# design.net
KiCad netlist of a schematic drawn in EasyEDA Pro
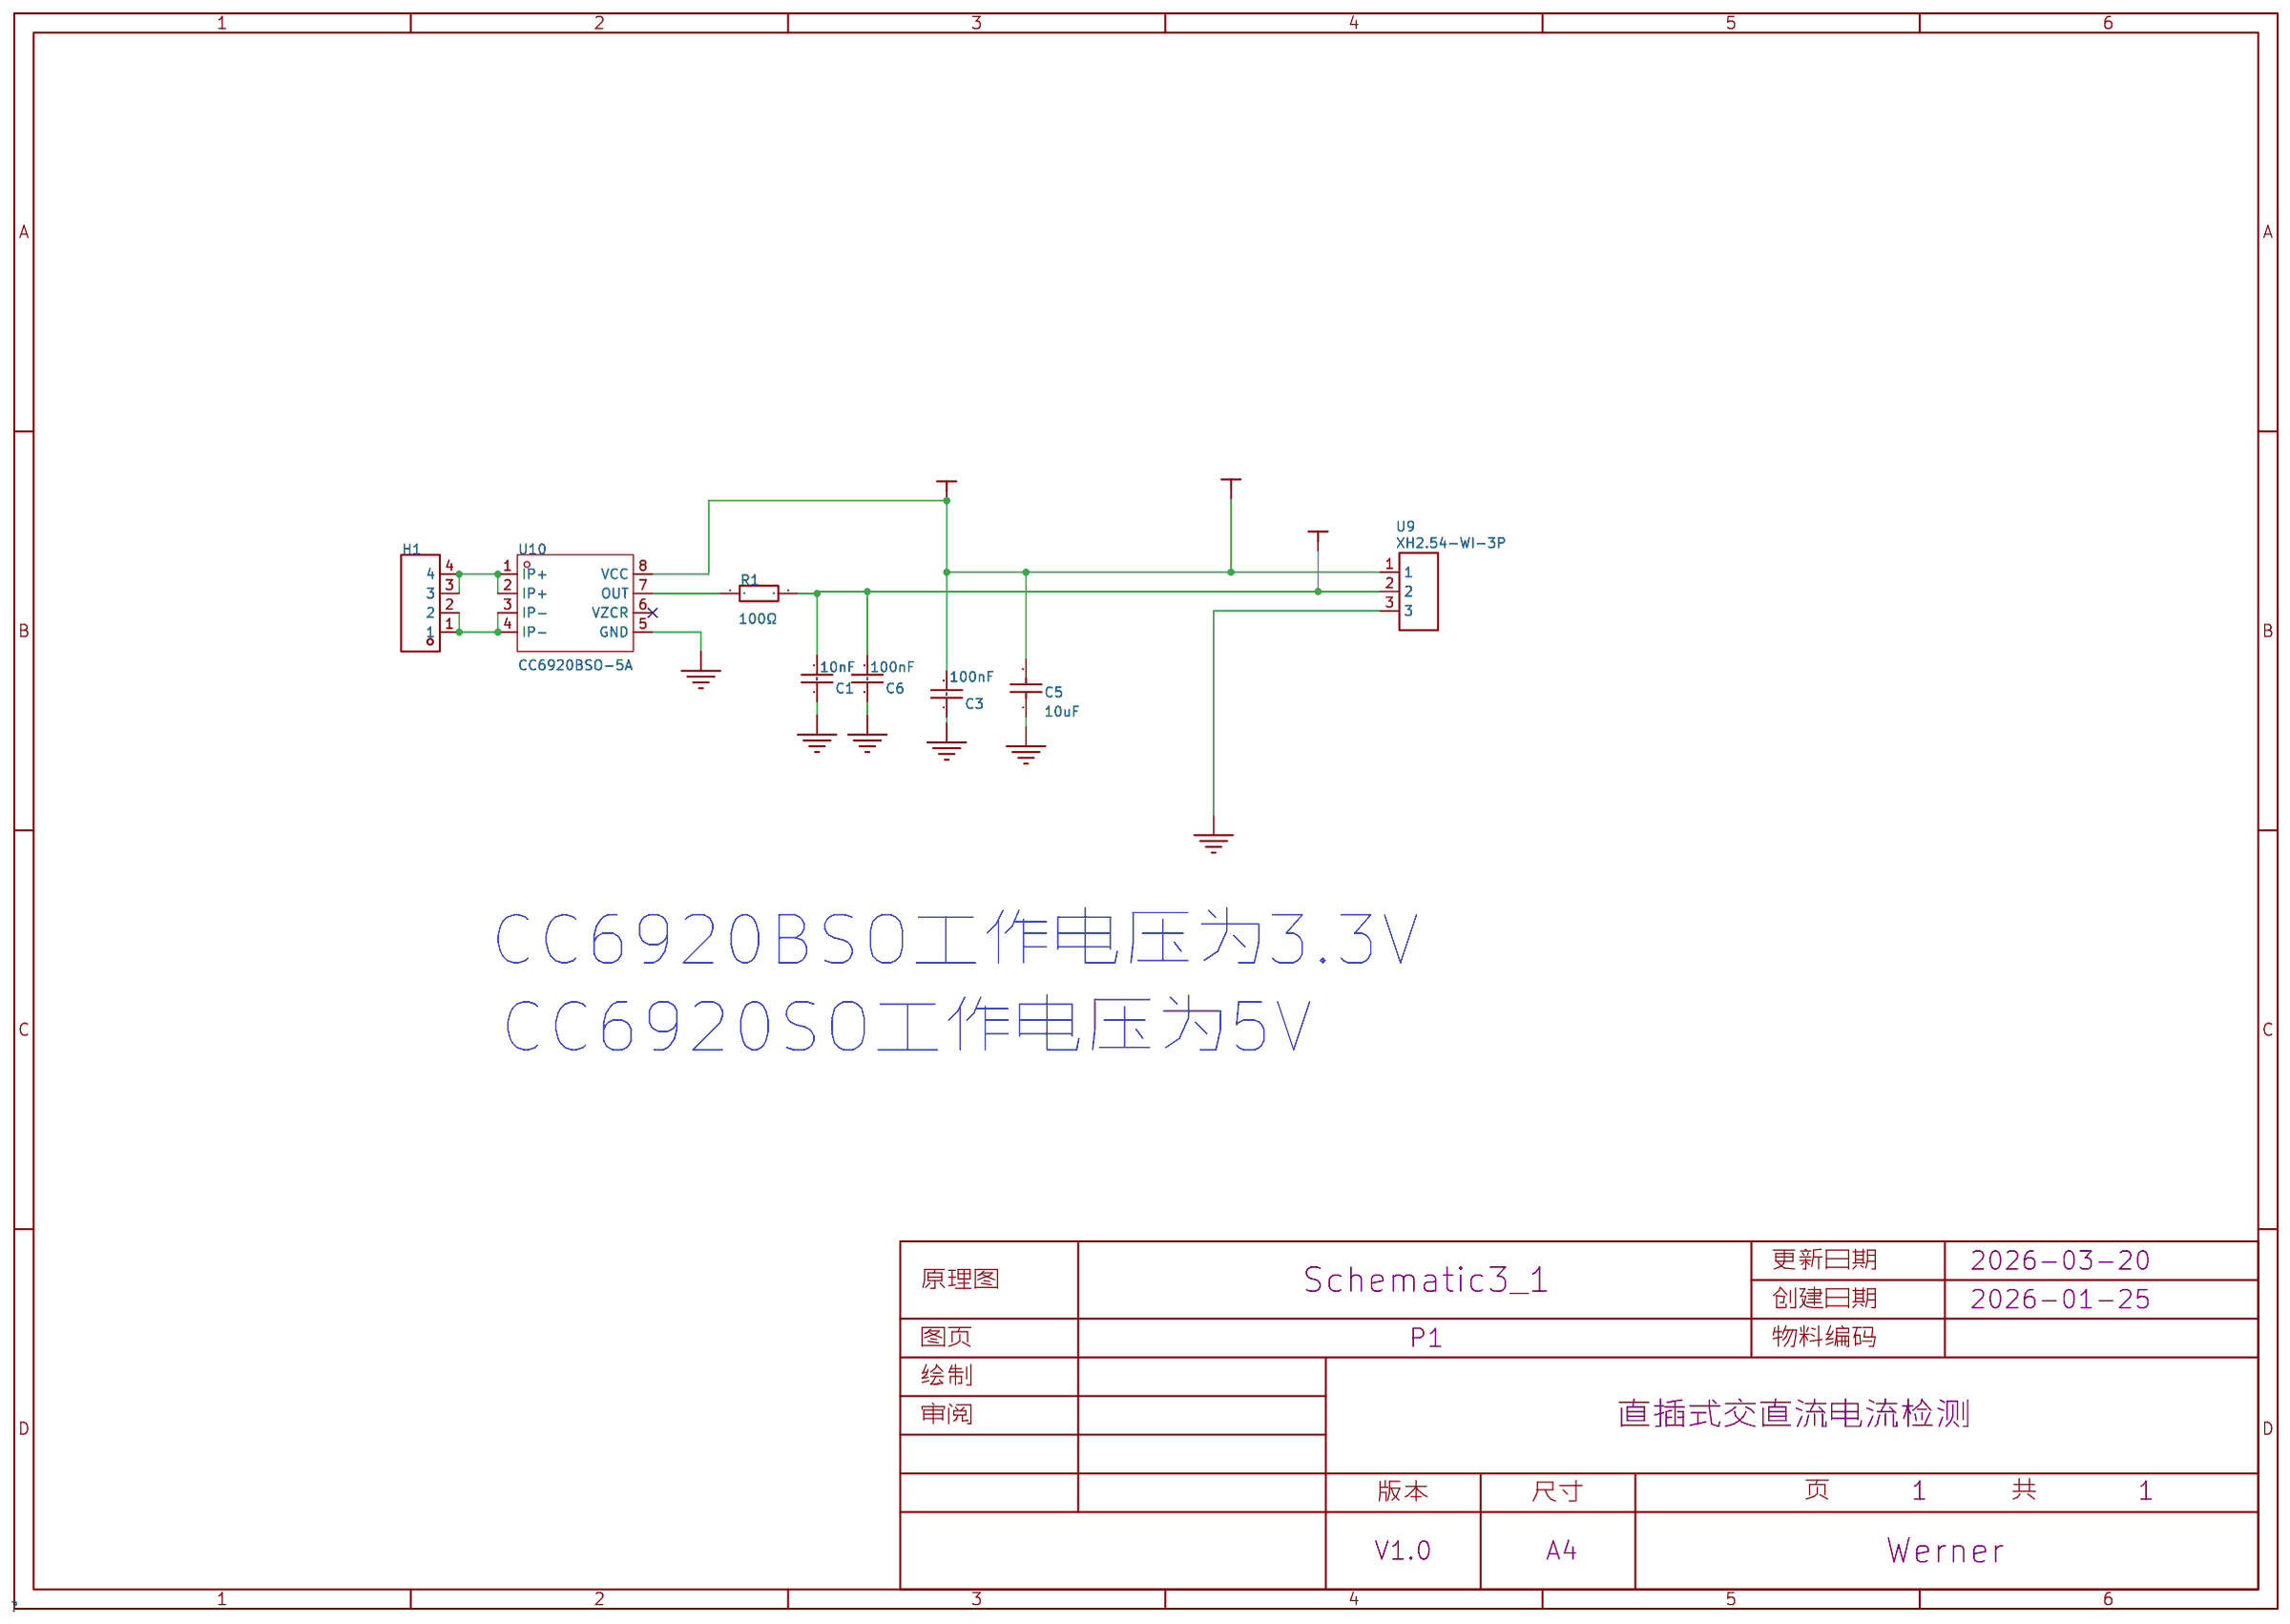
[diagram p0: schematic sheet]

(export (version "E")
  (design (tool "Eeschema 10.0.6"))
  (components
    (comp (ref "C1")
      (value "10nF")
      (footprint "easyedapro:C0603")
      (libsource (lib "easyedapro") (part "C0603"))
    )
    (comp (ref "C3")
      (value "100nF")
      (footprint "easyedapro:C0603")
      (libsource (lib "easyedapro") (part "C0603"))
    )
    (comp (ref "C5")
      (value "10uF")
      (footprint "easyedapro:C1206")
      (fields
        (field (name "Manufacturer Part") "CL31B104KBCNNNC")
        (field (name "Manufacturer") "SAMSUNG(三星)")
      )
      (libsource (lib "easyedapro") (part "C1206"))
    )
    (comp (ref "C6")
      (value "100nF")
      (footprint "easyedapro:C0603")
      (libsource (lib "easyedapro") (part "C0603"))
    )
    (comp (ref "H1")
      (value "PZ254V-11-04P")
      (footprint "easyedapro:HDR-TH_4P-P2.54-V-M")
      (fields (field (name "Manufacturer") "XFCN(兴飞)"))
      (libsource (lib "easyedapro") (part "PZ254V-11-04P"))
    )
    (comp (ref "R1")
      (value "100Ω")
      (footprint "easyedapro:Res_0603")
      (libsource (lib "easyedapro") (part "R0603"))
    )
    (comp (ref "U9")
      (value "XH2.54-WI-3P")
      (footprint "easyedapro:CONN-TH_XH2.54-WI-3P")
      (libsource (lib "easyedapro") (part "XH2.54-WI-3P"))
    )
    (comp (ref "U10")
      (value "CC6920BSO-5A")
      (footprint "easyedapro:SOP-8_L4.9-W3.9-P1.27-LS6.0-BL")
      (description "电流测量范围:-5A~5A;隔离耐压:3500Vrms;灵敏度:264mV/A;")
      (fields (field (name "Manufacturer") "CrossChip(成都芯进)"))
      (libsource (lib "easyedapro") (part "CC6920BSO-5A"))
    )
  )
  (nets
    (net (code "1") (name "3.3V") (class "Default")
      (node (ref "C3") (pin "2") (pinfunction "2_2") (pintype "input"))
      (node (ref "C5") (pin "2") (pinfunction "2_2") (pintype "input"))
      (node (ref "U10") (pin "8") (pinfunction "VCC_8") (pintype "unspecified"))
      (node (ref "U9") (pin "1") (pinfunction "1_1") (pintype "unspecified"))
    )
    (net (code "2") (name "GND") (class "Default")
      (node (ref "C1") (pin "1") (pinfunction "1_1") (pintype "input"))
      (node (ref "C3") (pin "1") (pinfunction "1_1") (pintype "input"))
      (node (ref "C5") (pin "1") (pinfunction "1_1") (pintype "input"))
      (node (ref "C6") (pin "1") (pinfunction "1_1") (pintype "input"))
      (node (ref "U10") (pin "5") (pinfunction "GND_5") (pintype "unspecified"))
      (node (ref "U9") (pin "3") (pinfunction "3_3") (pintype "unspecified"))
    )
    (net (code "3") (name "Net-(H1-Pad1)") (class "Default")
      (node (ref "H1") (pin "1") (pinfunction "1_1") (pintype "unspecified"))
      (node (ref "H1") (pin "2") (pinfunction "2_2") (pintype "unspecified"))
      (node (ref "U10") (pin "3") (pinfunction "IP-_3") (pintype "unspecified"))
      (node (ref "U10") (pin "4") (pinfunction "IP-_4") (pintype "unspecified"))
    )
    (net (code "4") (name "Net-(H1-Pad3)") (class "Default")
      (node (ref "H1") (pin "3") (pinfunction "3_3") (pintype "unspecified"))
      (node (ref "H1") (pin "4") (pinfunction "4_4") (pintype "unspecified"))
      (node (ref "U10") (pin "1") (pinfunction "IP+_1") (pintype "unspecified"))
      (node (ref "U10") (pin "2") (pinfunction "IP+_2") (pintype "unspecified"))
    )
    (net (code "5") (name "Net-(U10-OUT)") (class "Default")
      (node (ref "R1") (pin "1") (pinfunction "1_1") (pintype "input"))
      (node (ref "U10") (pin "7") (pinfunction "OUT_7") (pintype "unspecified"))
    )
    (net (code "6") (name "VOUT") (class "Default")
      (node (ref "C1") (pin "2") (pinfunction "2_2") (pintype "input"))
      (node (ref "C6") (pin "2") (pinfunction "2_2") (pintype "input"))
      (node (ref "R1") (pin "2") (pinfunction "2_2") (pintype "input"))
      (node (ref "U9") (pin "2") (pinfunction "2_2") (pintype "unspecified"))
    )
    (net (code "7") (name "unconnected-(U10-VZCR-Pad6)") (class "Default")
      (node (ref "U10") (pin "6") (pinfunction "VZCR_6") (pintype "unspecified+no_connect"))
    )
  )
)
